# BOC_SRAM.net
KiCad netlist of a schematic drawn in Altium Designer
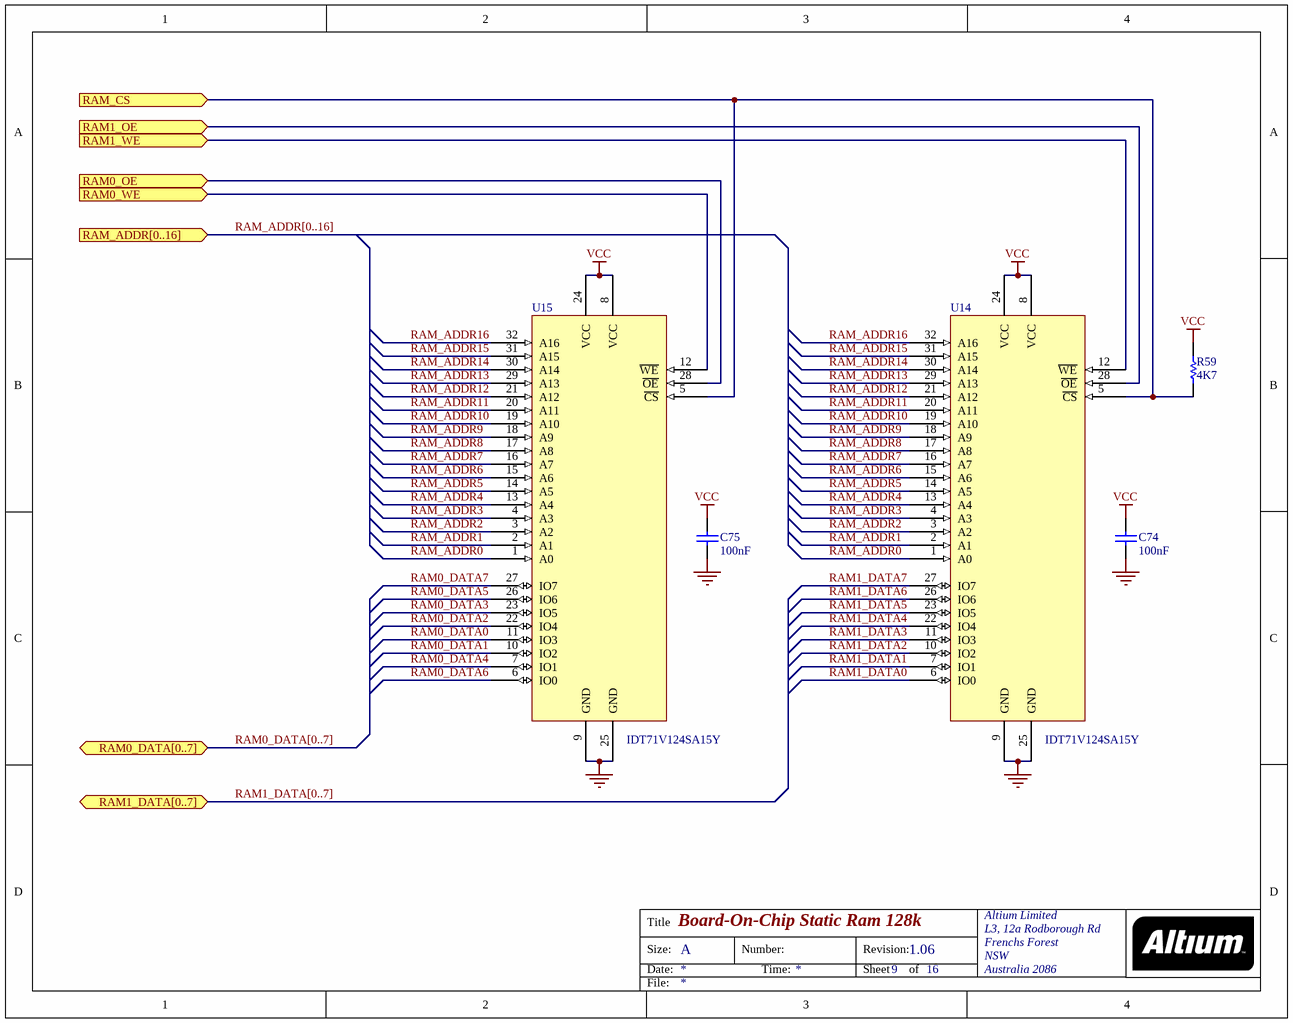
[diagram p0: BOC_SRAM.SchDoc]

(export (version "E")
  (design (tool "Eeschema 10.0.6"))
  (components
    (comp (ref "C74")
      (value "100nF")
      (footprint "Altium Nanoboard Project:CC2012-0805")
      (description "Capacitor")
      (libsource (lib "Altium Nanoboard Project") (part "CAP"))
    )
    (comp (ref "C75")
      (value "100nF")
      (footprint "Altium Nanoboard Project:CC2012-0805")
      (description "Capacitor")
      (libsource (lib "Altium Nanoboard Project") (part "CAP"))
    )
    (comp (ref "R59")
      (value "4K7")
      (footprint "Altium Nanoboard Project:CC2012-0805")
      (description "Resistor")
      (libsource (lib "Altium Nanoboard Project") (part "RES"))
    )
    (comp (ref "U14")
      (value "IDT71V124SA15Y")
      (footprint "Altium Nanoboard Project:SO-J32")
      (description "128K x 8 bit Fast Static RAM")
      (libsource (lib "Altium Nanoboard Project") (part "IDT71V124SA15Y"))
    )
    (comp (ref "U15")
      (value "IDT71V124SA15Y")
      (footprint "Altium Nanoboard Project:SO-J32")
      (description "128K x 8 bit Fast Static RAM")
      (libsource (lib "Altium Nanoboard Project") (part "IDT71V124SA15Y"))
    )
  )
  (nets
    (net (code "1") (name "/RAM0_DATA0") (class "Default")
      (node (ref "U15") (pin "11") (pinfunction "IO3_11") (pintype "bidirectional"))
    )
    (net (code "2") (name "/RAM0_DATA1") (class "Default")
      (node (ref "U15") (pin "10") (pinfunction "IO2_10") (pintype "bidirectional"))
    )
    (net (code "3") (name "/RAM0_DATA2") (class "Default")
      (node (ref "U15") (pin "22") (pinfunction "IO4_22") (pintype "bidirectional"))
    )
    (net (code "4") (name "/RAM0_DATA3") (class "Default")
      (node (ref "U15") (pin "23") (pinfunction "IO5_23") (pintype "bidirectional"))
    )
    (net (code "5") (name "/RAM0_DATA4") (class "Default")
      (node (ref "U15") (pin "7") (pinfunction "IO1_7") (pintype "bidirectional"))
    )
    (net (code "6") (name "/RAM0_DATA5") (class "Default")
      (node (ref "U15") (pin "26") (pinfunction "IO6_26") (pintype "bidirectional"))
    )
    (net (code "7") (name "/RAM0_DATA6") (class "Default")
      (node (ref "U15") (pin "6") (pinfunction "IO0_6") (pintype "bidirectional"))
    )
    (net (code "8") (name "/RAM0_DATA7") (class "Default")
      (node (ref "U15") (pin "27") (pinfunction "IO7_27") (pintype "bidirectional"))
    )
    (net (code "10") (name "/RAM0_OE") (class "Default")
      (node (ref "U15") (pin "28") (pinfunction "~{OE}_28") (pintype "input"))
    )
    (net (code "11") (name "/RAM0_WE") (class "Default")
      (node (ref "U15") (pin "12") (pinfunction "~{WE}_12") (pintype "input"))
    )
    (net (code "12") (name "/RAM1_DATA0") (class "Default")
      (node (ref "U14") (pin "6") (pinfunction "IO0_6") (pintype "bidirectional"))
    )
    (net (code "13") (name "/RAM1_DATA1") (class "Default")
      (node (ref "U14") (pin "7") (pinfunction "IO1_7") (pintype "bidirectional"))
    )
    (net (code "14") (name "/RAM1_DATA2") (class "Default")
      (node (ref "U14") (pin "10") (pinfunction "IO2_10") (pintype "bidirectional"))
    )
    (net (code "15") (name "/RAM1_DATA3") (class "Default")
      (node (ref "U14") (pin "11") (pinfunction "IO3_11") (pintype "bidirectional"))
    )
    (net (code "16") (name "/RAM1_DATA4") (class "Default")
      (node (ref "U14") (pin "22") (pinfunction "IO4_22") (pintype "bidirectional"))
    )
    (net (code "17") (name "/RAM1_DATA5") (class "Default")
      (node (ref "U14") (pin "23") (pinfunction "IO5_23") (pintype "bidirectional"))
    )
    (net (code "18") (name "/RAM1_DATA6") (class "Default")
      (node (ref "U14") (pin "26") (pinfunction "IO6_26") (pintype "bidirectional"))
    )
    (net (code "19") (name "/RAM1_DATA7") (class "Default")
      (node (ref "U14") (pin "27") (pinfunction "IO7_27") (pintype "bidirectional"))
    )
    (net (code "21") (name "/RAM1_OE") (class "Default")
      (node (ref "U14") (pin "28") (pinfunction "~{OE}_28") (pintype "input"))
    )
    (net (code "22") (name "/RAM1_WE") (class "Default")
      (node (ref "U14") (pin "12") (pinfunction "~{WE}_12") (pintype "input"))
    )
    (net (code "23") (name "/RAM_ADDR0") (class "Default")
      (node (ref "U14") (pin "1") (pinfunction "A0_1") (pintype "input"))
      (node (ref "U15") (pin "1") (pinfunction "A0_1") (pintype "input"))
    )
    (net (code "24") (name "/RAM_ADDR1") (class "Default")
      (node (ref "U14") (pin "2") (pinfunction "A1_2") (pintype "input"))
      (node (ref "U15") (pin "2") (pinfunction "A1_2") (pintype "input"))
    )
    (net (code "25") (name "/RAM_ADDR2") (class "Default")
      (node (ref "U14") (pin "3") (pinfunction "A2_3") (pintype "input"))
      (node (ref "U15") (pin "3") (pinfunction "A2_3") (pintype "input"))
    )
    (net (code "26") (name "/RAM_ADDR3") (class "Default")
      (node (ref "U14") (pin "4") (pinfunction "A3_4") (pintype "input"))
      (node (ref "U15") (pin "4") (pinfunction "A3_4") (pintype "input"))
    )
    (net (code "27") (name "/RAM_ADDR4") (class "Default")
      (node (ref "U14") (pin "13") (pinfunction "A4_13") (pintype "input"))
      (node (ref "U15") (pin "13") (pinfunction "A4_13") (pintype "input"))
    )
    (net (code "28") (name "/RAM_ADDR5") (class "Default")
      (node (ref "U14") (pin "14") (pinfunction "A5_14") (pintype "input"))
      (node (ref "U15") (pin "14") (pinfunction "A5_14") (pintype "input"))
    )
    (net (code "29") (name "/RAM_ADDR6") (class "Default")
      (node (ref "U14") (pin "15") (pinfunction "A6_15") (pintype "input"))
      (node (ref "U15") (pin "15") (pinfunction "A6_15") (pintype "input"))
    )
    (net (code "30") (name "/RAM_ADDR7") (class "Default")
      (node (ref "U14") (pin "16") (pinfunction "A7_16") (pintype "input"))
      (node (ref "U15") (pin "16") (pinfunction "A7_16") (pintype "input"))
    )
    (net (code "31") (name "/RAM_ADDR8") (class "Default")
      (node (ref "U14") (pin "17") (pinfunction "A8_17") (pintype "input"))
      (node (ref "U15") (pin "17") (pinfunction "A8_17") (pintype "input"))
    )
    (net (code "32") (name "/RAM_ADDR9") (class "Default")
      (node (ref "U14") (pin "18") (pinfunction "A9_18") (pintype "input"))
      (node (ref "U15") (pin "18") (pinfunction "A9_18") (pintype "input"))
    )
    (net (code "33") (name "/RAM_ADDR10") (class "Default")
      (node (ref "U14") (pin "19") (pinfunction "A10_19") (pintype "input"))
      (node (ref "U15") (pin "19") (pinfunction "A10_19") (pintype "input"))
    )
    (net (code "34") (name "/RAM_ADDR11") (class "Default")
      (node (ref "U14") (pin "20") (pinfunction "A11_20") (pintype "input"))
      (node (ref "U15") (pin "20") (pinfunction "A11_20") (pintype "input"))
    )
    (net (code "35") (name "/RAM_ADDR12") (class "Default")
      (node (ref "U14") (pin "21") (pinfunction "A12_21") (pintype "input"))
      (node (ref "U15") (pin "21") (pinfunction "A12_21") (pintype "input"))
    )
    (net (code "36") (name "/RAM_ADDR13") (class "Default")
      (node (ref "U14") (pin "29") (pinfunction "A13_29") (pintype "input"))
      (node (ref "U15") (pin "29") (pinfunction "A13_29") (pintype "input"))
    )
    (net (code "37") (name "/RAM_ADDR14") (class "Default")
      (node (ref "U14") (pin "30") (pinfunction "A14_30") (pintype "input"))
      (node (ref "U15") (pin "30") (pinfunction "A14_30") (pintype "input"))
    )
    (net (code "38") (name "/RAM_ADDR15") (class "Default")
      (node (ref "U14") (pin "31") (pinfunction "A15_31") (pintype "input"))
      (node (ref "U15") (pin "31") (pinfunction "A15_31") (pintype "input"))
    )
    (net (code "39") (name "/RAM_ADDR16") (class "Default")
      (node (ref "U14") (pin "32") (pinfunction "A16_32") (pintype "input"))
      (node (ref "U15") (pin "32") (pinfunction "A16_32") (pintype "input"))
    )
    (net (code "41") (name "/RAM_CS") (class "Default")
      (node (ref "R59") (pin "2") (pinfunction "2_2") (pintype "passive"))
      (node (ref "U14") (pin "5") (pinfunction "~{CS}_5") (pintype "input"))
      (node (ref "U15") (pin "5") (pinfunction "~{CS}_5") (pintype "input"))
    )
    (net (code "42") (name "GND") (class "Default")
      (node (ref "C74") (pin "2") (pinfunction "2_2") (pintype "passive"))
      (node (ref "C75") (pin "2") (pinfunction "2_2") (pintype "passive"))
      (node (ref "U14") (pin "25") (pinfunction "GND_25") (pintype "power_in"))
      (node (ref "U14") (pin "9") (pinfunction "GND_9") (pintype "power_in"))
      (node (ref "U15") (pin "25") (pinfunction "GND_25") (pintype "power_in"))
      (node (ref "U15") (pin "9") (pinfunction "GND_9") (pintype "power_in"))
    )
    (net (code "43") (name "VCC") (class "Default")
      (node (ref "C74") (pin "1") (pinfunction "1_1") (pintype "passive"))
      (node (ref "C75") (pin "1") (pinfunction "1_1") (pintype "passive"))
      (node (ref "R59") (pin "1") (pinfunction "1_1") (pintype "passive"))
      (node (ref "U14") (pin "24") (pinfunction "VCC_24") (pintype "power_in"))
      (node (ref "U14") (pin "8") (pinfunction "VCC_8") (pintype "power_in"))
      (node (ref "U15") (pin "24") (pinfunction "VCC_24") (pintype "power_in"))
      (node (ref "U15") (pin "8") (pinfunction "VCC_8") (pintype "power_in"))
    )
  )
)
